# XRACER-FMU-R07.net
KiCad netlist of a schematic drawn in Altium Designer
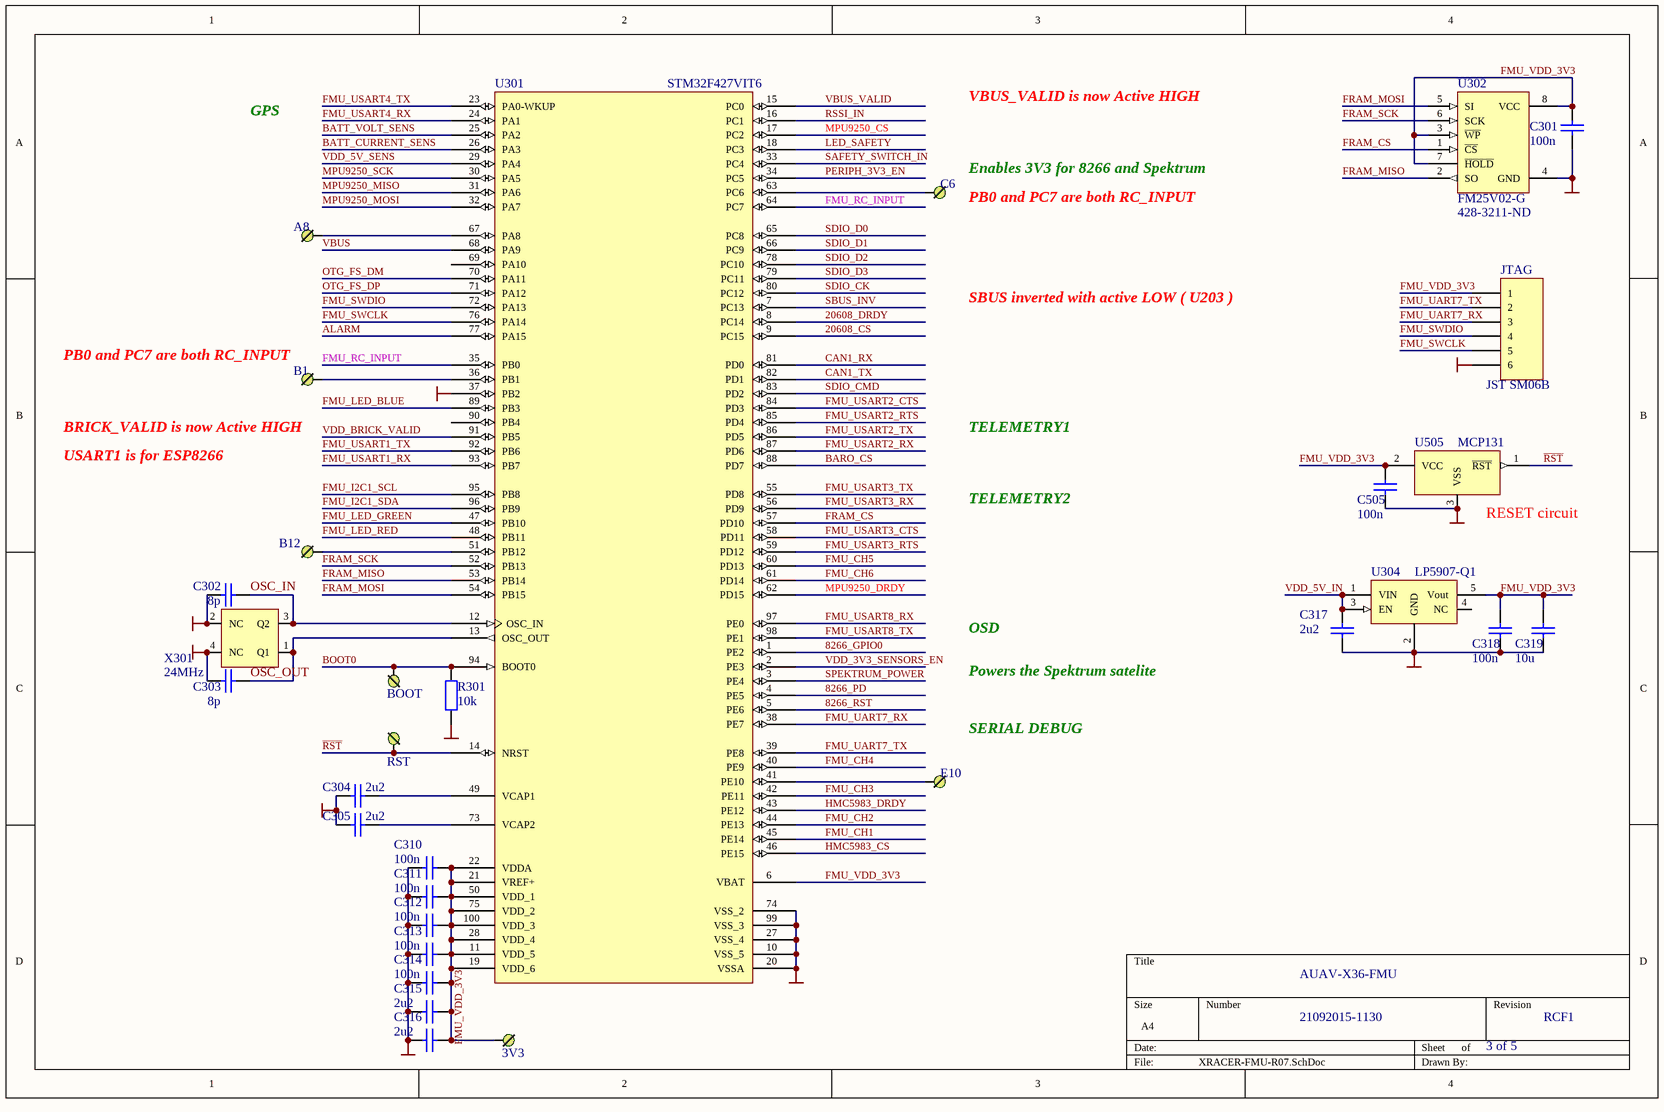
[diagram p0: XRACER-FMU-R07.SchDoc]

(export (version "E")
  (design (tool "Eeschema 10.0.6"))
  (components
    (comp (ref "3V3") (value "3V3") (footprint "PAD1") (libsource (lib "My_Altium") (part "PLUG")))
    (comp (ref "A8") (value "BOOT") (footprint "PAD1") (libsource (lib "My_Altium") (part "PLUG")))
    (comp (ref "B1") (value "BOOT") (footprint "PAD1") (libsource (lib "My_Altium") (part "PLUG")))
    (comp (ref "B12") (value "BOOT") (footprint "PAD1") (libsource (lib "My_Altium") (part "PLUG")))
    (comp (ref "BOOT") (value "BOOT") (footprint "PAD1") (libsource (lib "My_Altium") (part "PLUG")))
    (comp (ref "C6") (value "BOOT") (footprint "PAD1") (libsource (lib "My_Altium") (part "PLUG")))
    (comp (ref "C301")
      (value "100n")
      (footprint "0402A")
      (description "Capacitor")
      (fields (field (name "PUBLISHER") "Altium Limited"))
      (libsource (lib "Miscellaneous Devices") (part "Cap"))
    )
    (comp (ref "C302")
      (value "8p")
      (footprint "0603A")
      (description "Capacitor")
      (fields (field (name "PUBLISHER") "Altium Limited"))
      (libsource (lib "Miscellaneous Devices") (part "Cap"))
    )
    (comp (ref "C303")
      (value "8p")
      (footprint "0603A")
      (description "Capacitor")
      (fields (field (name "PUBLISHER") "Altium Limited"))
      (libsource (lib "Miscellaneous Devices") (part "Cap"))
    )
    (comp (ref "C304")
      (value "2u2")
      (footprint "0402A")
      (description "Capacitor")
      (fields (field (name "PUBLISHER") "Altium Limited"))
      (libsource (lib "Miscellaneous Devices") (part "Cap"))
    )
    (comp (ref "C305")
      (value "2u2")
      (footprint "0402A")
      (description "Capacitor")
      (fields (field (name "PUBLISHER") "Altium Limited"))
      (libsource (lib "Miscellaneous Devices") (part "Cap"))
    )
    (comp (ref "C310")
      (value "100n")
      (footprint "0402A")
      (description "Capacitor")
      (fields (field (name "PUBLISHER") "Altium Limited"))
      (libsource (lib "Miscellaneous Devices") (part "Cap"))
    )
    (comp (ref "C311")
      (value "100n")
      (footprint "0402A")
      (description "Capacitor")
      (fields (field (name "PUBLISHER") "Altium Limited"))
      (libsource (lib "Miscellaneous Devices") (part "Cap"))
    )
    (comp (ref "C312")
      (value "100n")
      (footprint "0402A")
      (description "Capacitor")
      (fields (field (name "PUBLISHER") "Altium Limited"))
      (libsource (lib "Miscellaneous Devices") (part "Cap"))
    )
    (comp (ref "C313")
      (value "100n")
      (footprint "0402A")
      (description "Capacitor")
      (fields (field (name "PUBLISHER") "Altium Limited"))
      (libsource (lib "Miscellaneous Devices") (part "Cap"))
    )
    (comp (ref "C314")
      (value "100n")
      (footprint "0402A")
      (description "Capacitor")
      (fields (field (name "PUBLISHER") "Altium Limited"))
      (libsource (lib "Miscellaneous Devices") (part "Cap"))
    )
    (comp (ref "C315")
      (value "2u2")
      (footprint "0402A")
      (description "Capacitor")
      (fields (field (name "PUBLISHER") "Altium Limited"))
      (libsource (lib "Miscellaneous Devices") (part "Cap"))
    )
    (comp (ref "C316")
      (value "2u2")
      (footprint "0402A")
      (description "Capacitor")
      (fields (field (name "PUBLISHER") "Altium Limited"))
      (libsource (lib "Miscellaneous Devices") (part "Cap"))
    )
    (comp (ref "C317")
      (value "2u2")
      (footprint "0603A")
      (description "Capacitor")
      (fields (field (name "PUBLISHER") "Altium Limited"))
      (libsource (lib "Miscellaneous Devices") (part "Cap"))
    )
    (comp (ref "C318")
      (value "100n")
      (footprint "0603A")
      (description "Capacitor")
      (fields (field (name "PUBLISHER") "Altium Limited"))
      (libsource (lib "Miscellaneous Devices") (part "Cap"))
    )
    (comp (ref "C319")
      (value "10u")
      (footprint "0603A")
      (description "Capacitor")
      (fields (field (name "PUBLISHER") "Altium Limited"))
      (libsource (lib "Miscellaneous Devices") (part "Cap"))
    )
    (comp (ref "C505")
      (value "100n")
      (footprint "0402A")
      (description "Capacitor")
      (fields (field (name "PUBLISHER") "Altium Limited"))
      (libsource (lib "Miscellaneous Devices") (part "Cap"))
    )
    (comp (ref "E10") (value "BOOT") (footprint "PAD1") (libsource (lib "My_Altium") (part "PLUG")))
    (comp (ref "JTAG")
      (value "JST SM06B")
      (footprint "SM06B-SRSH-TB")
      (description "Header, 6-Pin")
      (fields (field (name "PUBLISHER") "Altium Limited"))
      (libsource (lib "Miscellaneous Connectors") (part "Header 6"))
    )
    (comp (ref "R301")
      (value "10k")
      (footprint "0402A")
      (description "Resistor")
      (fields (field (name "PUBLISHER") "Altium Limited"))
      (libsource (lib "Miscellaneous Devices") (part "Res2"))
    )
    (comp (ref "RST") (value "BOOT") (footprint "PAD1") (libsource (lib "My_Altium") (part "PLUG")))
    (comp (ref "U301")
      (value "STM32F427VIT6")
      (footprint "LQFP100_L")
      (description "STM32 ARM-based 32-bit MCU with 64 Kbytes Flash, 100-pin LQFP, Industrial Temperature")
      (fields (field (name "PUBLISHER") "Altium Limited"))
      (libsource (lib "ST Microcontroller 32-Bit STM32") (part "STM32F103VBT6"))
    )
    (comp (ref "U302")
      (value "FM25V02-G")
      (footprint "SO-8_N")
      (fields (field (name "SUPPLIER PART NUMBER") "428-3211-ND"))
      (libsource (lib "My_Altium") (part "AT45DB161D-MU"))
    )
    (comp (ref "U304")
      (value "LP5907-Q1")
      (footprint "SOT23-5")
      (libsource (lib "My_Altium") (part "LP5907-Q1"))
    )
    (comp (ref "U505") (value "MCP131") (footprint "SOT-323") (libsource (lib "My_Altium") (part "MCP102")))
    (comp (ref "X301")
      (value "24MHz")
      (footprint "Crystal_2.5x2")
      (libsource (lib "My_Altium") (part "Crystal_4pin"))
    )
  )
  (nets
    (net (code "1") (name "/8266_GPIO0") (class "Default")
      (node (ref "U301") (pin "1") (pinfunction "PE2_1") (pintype "bidirectional"))
    )
    (net (code "2") (name "/8266_PD") (class "Default")
      (node (ref "U301") (pin "4") (pinfunction "PE5_4") (pintype "bidirectional"))
    )
    (net (code "3") (name "/8266_RST") (class "Default")
      (node (ref "U301") (pin "5") (pinfunction "PE6_5") (pintype "bidirectional"))
    )
    (net (code "4") (name "/20608_CS") (class "Default")
      (node (ref "U301") (pin "9") (pinfunction "PC15_9") (pintype "bidirectional"))
    )
    (net (code "5") (name "/20608_DRDY") (class "Default")
      (node (ref "U301") (pin "8") (pinfunction "PC14_8") (pintype "bidirectional"))
    )
    (net (code "6") (name "/ALARM") (class "Default")
      (node (ref "U301") (pin "77") (pinfunction "PA15_77") (pintype "bidirectional"))
    )
    (net (code "7") (name "/BARO_CS") (class "Default")
      (node (ref "U301") (pin "88") (pinfunction "PD7_88") (pintype "bidirectional"))
    )
    (net (code "8") (name "/BATT_CURRENT_SENS") (class "Default")
      (node (ref "U301") (pin "26") (pinfunction "PA3_26") (pintype "bidirectional"))
    )
    (net (code "9") (name "/BATT_VOLT_SENS") (class "Default")
      (node (ref "U301") (pin "25") (pinfunction "PA2_25") (pintype "bidirectional"))
    )
    (net (code "10") (name "/BOOT0") (class "Default")
      (node (ref "BOOT") (pin "1") (pintype "passive"))
      (node (ref "R301") (pin "1") (pinfunction "1_1") (pintype "passive"))
      (node (ref "U301") (pin "94") (pinfunction "BOOT0_94") (pintype "input"))
    )
    (net (code "11") (name "/CAN1_RX") (class "Default")
      (node (ref "U301") (pin "81") (pinfunction "PD0_81") (pintype "bidirectional"))
    )
    (net (code "12") (name "/CAN1_TX") (class "Default")
      (node (ref "U301") (pin "82") (pinfunction "PD1_82") (pintype "bidirectional"))
    )
    (net (code "13") (name "/FMU_CH1") (class "Default")
      (node (ref "U301") (pin "45") (pinfunction "PE14_45") (pintype "bidirectional"))
    )
    (net (code "14") (name "/FMU_CH2") (class "Default")
      (node (ref "U301") (pin "44") (pinfunction "PE13_44") (pintype "bidirectional"))
    )
    (net (code "15") (name "/FMU_CH3") (class "Default")
      (node (ref "U301") (pin "42") (pinfunction "PE11_42") (pintype "bidirectional"))
    )
    (net (code "16") (name "/FMU_CH4") (class "Default")
      (node (ref "U301") (pin "40") (pinfunction "PE9_40") (pintype "bidirectional"))
    )
    (net (code "17") (name "/FMU_CH5") (class "Default")
      (node (ref "U301") (pin "60") (pinfunction "PD13_60") (pintype "bidirectional"))
    )
    (net (code "18") (name "/FMU_CH6") (class "Default")
      (node (ref "U301") (pin "61") (pinfunction "PD14_61") (pintype "bidirectional"))
    )
    (net (code "19") (name "/FMU_I2C1_SCL") (class "Default")
      (node (ref "U301") (pin "95") (pinfunction "PB8_95") (pintype "bidirectional"))
    )
    (net (code "20") (name "/FMU_I2C1_SDA") (class "Default")
      (node (ref "U301") (pin "96") (pinfunction "PB9_96") (pintype "bidirectional"))
    )
    (net (code "21") (name "/FMU_LED_BLUE") (class "Default")
      (node (ref "U301") (pin "89") (pinfunction "PB3_89") (pintype "bidirectional"))
    )
    (net (code "22") (name "/FMU_LED_GREEN") (class "Default")
      (node (ref "U301") (pin "47") (pinfunction "PB10_47") (pintype "bidirectional"))
    )
    (net (code "23") (name "/FMU_LED_RED") (class "Default")
      (node (ref "U301") (pin "48") (pinfunction "PB11_48") (pintype "bidirectional"))
    )
    (net (code "24") (name "/FMU_RC_INPUT") (class "Default")
      (node (ref "U301") (pin "35") (pinfunction "PB0_35") (pintype "bidirectional"))
      (node (ref "U301") (pin "64") (pinfunction "PC7_64") (pintype "bidirectional"))
    )
    (net (code "25") (name "/FMU_SWCLK") (class "Default")
      (node (ref "JTAG") (pin "5") (pinfunction "5_5") (pintype "passive"))
      (node (ref "U301") (pin "76") (pinfunction "PA14_76") (pintype "bidirectional"))
    )
    (net (code "26") (name "/FMU_SWDIO") (class "Default")
      (node (ref "JTAG") (pin "4") (pinfunction "4_4") (pintype "passive"))
      (node (ref "U301") (pin "72") (pinfunction "PA13_72") (pintype "bidirectional"))
    )
    (net (code "27") (name "/FMU_UART7_RX") (class "Default")
      (node (ref "JTAG") (pin "3") (pinfunction "3_3") (pintype "passive"))
      (node (ref "U301") (pin "38") (pinfunction "PE7_38") (pintype "bidirectional"))
    )
    (net (code "28") (name "/FMU_UART7_TX") (class "Default")
      (node (ref "JTAG") (pin "2") (pinfunction "2_2") (pintype "passive"))
      (node (ref "U301") (pin "39") (pinfunction "PE8_39") (pintype "bidirectional"))
    )
    (net (code "29") (name "/FMU_USART1_RX") (class "Default")
      (node (ref "U301") (pin "93") (pinfunction "PB7_93") (pintype "bidirectional"))
    )
    (net (code "30") (name "/FMU_USART1_TX") (class "Default")
      (node (ref "U301") (pin "92") (pinfunction "PB6_92") (pintype "bidirectional"))
    )
    (net (code "31") (name "/FMU_USART2_CTS") (class "Default")
      (node (ref "U301") (pin "84") (pinfunction "PD3_84") (pintype "bidirectional"))
    )
    (net (code "32") (name "/FMU_USART2_RTS") (class "Default")
      (node (ref "U301") (pin "85") (pinfunction "PD4_85") (pintype "bidirectional"))
    )
    (net (code "33") (name "/FMU_USART2_RX") (class "Default")
      (node (ref "U301") (pin "87") (pinfunction "PD6_87") (pintype "bidirectional"))
    )
    (net (code "34") (name "/FMU_USART2_TX") (class "Default")
      (node (ref "U301") (pin "86") (pinfunction "PD5_86") (pintype "bidirectional"))
    )
    (net (code "35") (name "/FMU_USART3_CTS") (class "Default")
      (node (ref "U301") (pin "58") (pinfunction "PD11_58") (pintype "bidirectional"))
    )
    (net (code "36") (name "/FMU_USART3_RTS") (class "Default")
      (node (ref "U301") (pin "59") (pinfunction "PD12_59") (pintype "bidirectional"))
    )
    (net (code "37") (name "/FMU_USART3_RX") (class "Default")
      (node (ref "U301") (pin "56") (pinfunction "PD9_56") (pintype "bidirectional"))
    )
    (net (code "38") (name "/FMU_USART3_TX") (class "Default")
      (node (ref "U301") (pin "55") (pinfunction "PD8_55") (pintype "bidirectional"))
    )
    (net (code "39") (name "/FMU_USART4_RX") (class "Default")
      (node (ref "U301") (pin "24") (pinfunction "PA1_24") (pintype "bidirectional"))
    )
    (net (code "40") (name "/FMU_USART4_TX") (class "Default")
      (node (ref "U301") (pin "23") (pinfunction "PA0-WKUP_23") (pintype "bidirectional"))
    )
    (net (code "41") (name "/FMU_USART8_RX") (class "Default")
      (node (ref "U301") (pin "97") (pinfunction "PE0_97") (pintype "bidirectional"))
    )
    (net (code "42") (name "/FMU_USART8_TX") (class "Default")
      (node (ref "U301") (pin "98") (pinfunction "PE1_98") (pintype "bidirectional"))
    )
    (net (code "43") (name "/FMU_VDD_3V3") (class "Default")
      (node (ref "3V3") (pin "1") (pintype "passive"))
      (node (ref "C301") (pin "2") (pinfunction "2_2") (pintype "passive"))
      (node (ref "C310") (pin "2") (pinfunction "2_2") (pintype "passive"))
      (node (ref "C311") (pin "2") (pinfunction "2_2") (pintype "passive"))
      (node (ref "C312") (pin "2") (pinfunction "2_2") (pintype "passive"))
      (node (ref "C313") (pin "2") (pinfunction "2_2") (pintype "passive"))
      (node (ref "C314") (pin "2") (pinfunction "2_2") (pintype "passive"))
      (node (ref "C315") (pin "2") (pinfunction "2_2") (pintype "passive"))
      (node (ref "C316") (pin "2") (pinfunction "2_2") (pintype "passive"))
      (node (ref "C318") (pin "2") (pinfunction "2_2") (pintype "passive"))
      (node (ref "C319") (pin "2") (pinfunction "2_2") (pintype "passive"))
      (node (ref "C505") (pin "2") (pinfunction "2_2") (pintype "passive"))
      (node (ref "JTAG") (pin "1") (pinfunction "1_1") (pintype "passive"))
      (node (ref "U301") (pin "100") (pinfunction "VDD_3_100") (pintype "power_in"))
      (node (ref "U301") (pin "11") (pinfunction "VDD_5_11") (pintype "power_in"))
      (node (ref "U301") (pin "19") (pinfunction "VDD_6_19") (pintype "power_in"))
      (node (ref "U301") (pin "21") (pinfunction "VREF+_21") (pintype "power_in"))
      (node (ref "U301") (pin "22") (pinfunction "VDDA_22") (pintype "power_in"))
      (node (ref "U301") (pin "28") (pinfunction "VDD_4_28") (pintype "power_in"))
      (node (ref "U301") (pin "50") (pinfunction "VDD_1_50") (pintype "power_in"))
      (node (ref "U301") (pin "6") (pinfunction "VBAT_6") (pintype "power_in"))
      (node (ref "U301") (pin "75") (pinfunction "VDD_2_75") (pintype "power_in"))
      (node (ref "U302") (pin "3") (pinfunction "~{WP}_3") (pintype "input"))
      (node (ref "U302") (pin "7") (pinfunction "~{HOLD}_7") (pintype "passive"))
      (node (ref "U302") (pin "8") (pinfunction "VCC_8") (pintype "power_in"))
      (node (ref "U304") (pin "5") (pinfunction "Vout_5") (pintype "power_in"))
      (node (ref "U505") (pin "2") (pinfunction "VCC_2") (pintype "power_in"))
    )
    (net (code "44") (name "/FRAM_CS") (class "Default")
      (node (ref "U301") (pin "57") (pinfunction "PD10_57") (pintype "bidirectional"))
      (node (ref "U302") (pin "1") (pinfunction "~{CS}_1") (pintype "input"))
    )
    (net (code "45") (name "/FRAM_MISO") (class "Default")
      (node (ref "U301") (pin "53") (pinfunction "PB14_53") (pintype "bidirectional"))
      (node (ref "U302") (pin "2") (pinfunction "SO_2") (pintype "output"))
    )
    (net (code "46") (name "/FRAM_MOSI") (class "Default")
      (node (ref "U301") (pin "54") (pinfunction "PB15_54") (pintype "bidirectional"))
      (node (ref "U302") (pin "5") (pinfunction "SI_5") (pintype "input"))
    )
    (net (code "47") (name "/FRAM_SCK") (class "Default")
      (node (ref "U301") (pin "52") (pinfunction "PB13_52") (pintype "bidirectional"))
      (node (ref "U302") (pin "6") (pinfunction "SCK_6") (pintype "input"))
    )
    (net (code "48") (name "/HMC5983_CS") (class "Default")
      (node (ref "U301") (pin "46") (pinfunction "PE15_46") (pintype "bidirectional"))
    )
    (net (code "49") (name "/HMC5983_DRDY") (class "Default")
      (node (ref "U301") (pin "43") (pinfunction "PE12_43") (pintype "bidirectional"))
    )
    (net (code "50") (name "/LED_SAFETY") (class "Default")
      (node (ref "U301") (pin "18") (pinfunction "PC3_18") (pintype "bidirectional"))
    )
    (net (code "51") (name "/MPU9250_CS") (class "Default")
      (node (ref "U301") (pin "17") (pinfunction "PC2_17") (pintype "bidirectional"))
    )
    (net (code "52") (name "/MPU9250_DRDY") (class "Default")
      (node (ref "U301") (pin "62") (pinfunction "PD15_62") (pintype "bidirectional"))
    )
    (net (code "53") (name "/MPU9250_MISO") (class "Default")
      (node (ref "U301") (pin "31") (pinfunction "PA6_31") (pintype "bidirectional"))
    )
    (net (code "54") (name "/MPU9250_MOSI") (class "Default")
      (node (ref "U301") (pin "32") (pinfunction "PA7_32") (pintype "bidirectional"))
    )
    (net (code "55") (name "/MPU9250_SCK") (class "Default")
      (node (ref "U301") (pin "30") (pinfunction "PA5_30") (pintype "bidirectional"))
    )
    (net (code "56") (name "/OSC_IN") (class "Default")
      (node (ref "C302") (pin "2") (pinfunction "2_2") (pintype "passive"))
      (node (ref "U301") (pin "12") (pinfunction "OSC_IN_12") (pintype "input"))
      (node (ref "X301") (pin "3") (pinfunction "Q2_3") (pintype "passive"))
    )
    (net (code "57") (name "/OSC_OUT") (class "Default")
      (node (ref "C303") (pin "2") (pinfunction "2_2") (pintype "passive"))
      (node (ref "U301") (pin "13") (pinfunction "OSC_OUT_13") (pintype "output"))
      (node (ref "X301") (pin "1") (pinfunction "Q1_1") (pintype "passive"))
    )
    (net (code "58") (name "/OTG_FS_DM") (class "Default")
      (node (ref "U301") (pin "70") (pinfunction "PA11_70") (pintype "bidirectional"))
    )
    (net (code "59") (name "/OTG_FS_DP") (class "Default")
      (node (ref "U301") (pin "71") (pinfunction "PA12_71") (pintype "bidirectional"))
    )
    (net (code "60") (name "/PERIPH_3V3_EN") (class "Default")
      (node (ref "U301") (pin "34") (pinfunction "PC5_34") (pintype "bidirectional"))
    )
    (net (code "61") (name "/RSSI_IN") (class "Default")
      (node (ref "U301") (pin "16") (pinfunction "PC1_16") (pintype "bidirectional"))
    )
    (net (code "62") (name "/SAFETY_SWITCH_IN") (class "Default")
      (node (ref "U301") (pin "33") (pinfunction "PC4_33") (pintype "bidirectional"))
    )
    (net (code "63") (name "/SBUS_INV") (class "Default")
      (node (ref "U301") (pin "7") (pinfunction "PC13_7") (pintype "bidirectional"))
    )
    (net (code "64") (name "/SDIO_CK") (class "Default")
      (node (ref "U301") (pin "80") (pinfunction "PC12_80") (pintype "bidirectional"))
    )
    (net (code "65") (name "/SDIO_CMD") (class "Default")
      (node (ref "U301") (pin "83") (pinfunction "PD2_83") (pintype "bidirectional"))
    )
    (net (code "66") (name "/SDIO_D0") (class "Default")
      (node (ref "U301") (pin "65") (pinfunction "PC8_65") (pintype "bidirectional"))
    )
    (net (code "67") (name "/SDIO_D1") (class "Default")
      (node (ref "U301") (pin "66") (pinfunction "PC9_66") (pintype "bidirectional"))
    )
    (net (code "68") (name "/SDIO_D2") (class "Default")
      (node (ref "U301") (pin "78") (pinfunction "PC10_78") (pintype "bidirectional"))
    )
    (net (code "69") (name "/SDIO_D3") (class "Default")
      (node (ref "U301") (pin "79") (pinfunction "PC11_79") (pintype "bidirectional"))
    )
    (net (code "70") (name "/SPEKTRUM_POWER") (class "Default")
      (node (ref "U301") (pin "3") (pinfunction "PE4_3") (pintype "bidirectional"))
    )
    (net (code "71") (name "/VBUS") (class "Default")
      (node (ref "U301") (pin "68") (pinfunction "PA9_68") (pintype "bidirectional"))
    )
    (net (code "72") (name "/VBUS_VALID") (class "Default")
      (node (ref "U301") (pin "15") (pinfunction "PC0_15") (pintype "bidirectional"))
    )
    (net (code "73") (name "/VDD_3V3_SENSORS_EN") (class "Default")
      (node (ref "U301") (pin "2") (pinfunction "PE3_2") (pintype "bidirectional"))
    )
    (net (code "74") (name "/VDD_5V_IN") (class "Default")
      (node (ref "C317") (pin "2") (pinfunction "2_2") (pintype "passive"))
      (node (ref "U304") (pin "1") (pinfunction "VIN_1") (pintype "power_in"))
      (node (ref "U304") (pin "3") (pinfunction "EN_3") (pintype "input"))
    )
    (net (code "75") (name "/VDD_5V_SENS") (class "Default")
      (node (ref "U301") (pin "29") (pinfunction "PA4_29") (pintype "bidirectional"))
    )
    (net (code "76") (name "/VDD_BRICK_VALID") (class "Default")
      (node (ref "U301") (pin "91") (pinfunction "PB5_91") (pintype "bidirectional"))
    )
    (net (code "77") (name "/~{RST}") (class "Default")
      (node (ref "RST") (pin "1") (pintype "passive"))
      (node (ref "U301") (pin "14") (pinfunction "NRST_14") (pintype "bidirectional"))
      (node (ref "U505") (pin "1") (pinfunction "~{RST}_1") (pintype "output"))
    )
    (net (code "78") (name "GND") (class "Default")
      (node (ref "C301") (pin "1") (pinfunction "1_1") (pintype "passive"))
      (node (ref "C302") (pin "1") (pinfunction "1_1") (pintype "passive"))
      (node (ref "C303") (pin "1") (pinfunction "1_1") (pintype "passive"))
      (node (ref "C304") (pin "2") (pinfunction "2_2") (pintype "passive"))
      (node (ref "C305") (pin "2") (pinfunction "2_2") (pintype "passive"))
      (node (ref "C310") (pin "1") (pinfunction "1_1") (pintype "passive"))
      (node (ref "C311") (pin "1") (pinfunction "1_1") (pintype "passive"))
      (node (ref "C312") (pin "1") (pinfunction "1_1") (pintype "passive"))
      (node (ref "C313") (pin "1") (pinfunction "1_1") (pintype "passive"))
      (node (ref "C314") (pin "1") (pinfunction "1_1") (pintype "passive"))
      (node (ref "C315") (pin "1") (pinfunction "1_1") (pintype "passive"))
      (node (ref "C316") (pin "1") (pinfunction "1_1") (pintype "passive"))
      (node (ref "C317") (pin "1") (pinfunction "1_1") (pintype "passive"))
      (node (ref "C318") (pin "1") (pinfunction "1_1") (pintype "passive"))
      (node (ref "C319") (pin "1") (pinfunction "1_1") (pintype "passive"))
      (node (ref "C505") (pin "1") (pinfunction "1_1") (pintype "passive"))
      (node (ref "JTAG") (pin "6") (pinfunction "6_6") (pintype "passive"))
      (node (ref "R301") (pin "2") (pinfunction "2_2") (pintype "passive"))
      (node (ref "U301") (pin "10") (pinfunction "VSS_5_10") (pintype "power_in"))
      (node (ref "U301") (pin "20") (pinfunction "VSSA_20") (pintype "power_in"))
      (node (ref "U301") (pin "27") (pinfunction "VSS_4_27") (pintype "power_in"))
      (node (ref "U301") (pin "37") (pinfunction "PB2_37") (pintype "bidirectional"))
      (node (ref "U301") (pin "74") (pinfunction "VSS_2_74") (pintype "power_in"))
      (node (ref "U301") (pin "99") (pinfunction "VSS_3_99") (pintype "power_in"))
      (node (ref "U302") (pin "4") (pinfunction "GND_4") (pintype "power_in"))
      (node (ref "U304") (pin "2") (pinfunction "GND_2") (pintype "power_in"))
      (node (ref "U505") (pin "3") (pinfunction "VSS_3") (pintype "power_in"))
      (node (ref "X301") (pin "2") (pinfunction "NC_2") (pintype "passive"))
      (node (ref "X301") (pin "4") (pinfunction "NC_4") (pintype "passive"))
    )
    (net (code "79") (name "Net-(U301-PA8)") (class "Default")
      (node (ref "A8") (pin "1") (pintype "passive"))
      (node (ref "U301") (pin "67") (pinfunction "PA8_67") (pintype "bidirectional"))
    )
    (net (code "80") (name "Net-(U301-PB1)") (class "Default")
      (node (ref "B1") (pin "1") (pintype "passive"))
      (node (ref "U301") (pin "36") (pinfunction "PB1_36") (pintype "bidirectional"))
    )
    (net (code "81") (name "Net-(U301-PB12)") (class "Default")
      (node (ref "B12") (pin "1") (pintype "passive"))
      (node (ref "U301") (pin "51") (pinfunction "PB12_51") (pintype "bidirectional"))
    )
    (net (code "82") (name "Net-(U301-PC6)") (class "Default")
      (node (ref "C6") (pin "1") (pintype "passive"))
      (node (ref "U301") (pin "63") (pinfunction "PC6_63") (pintype "bidirectional"))
    )
    (net (code "83") (name "Net-(U301-PE10)") (class "Default")
      (node (ref "E10") (pin "1") (pintype "passive"))
      (node (ref "U301") (pin "41") (pinfunction "PE10_41") (pintype "bidirectional"))
    )
    (net (code "84") (name "Net-(U301-VCAP1)") (class "Default")
      (node (ref "C304") (pin "1") (pinfunction "1_1") (pintype "passive"))
      (node (ref "U301") (pin "49") (pinfunction "VCAP1_49") (pintype "passive"))
    )
    (net (code "85") (name "Net-(U301-VCAP2)") (class "Default")
      (node (ref "C305") (pin "1") (pinfunction "1_1") (pintype "passive"))
      (node (ref "U301") (pin "73") (pinfunction "VCAP2_73") (pintype "passive"))
    )
    (net (code "86") (name "unconnected-(U301-PA10-Pad69)") (class "Default")
      (node (ref "U301") (pin "69") (pinfunction "PA10_69") (pintype "bidirectional"))
    )
    (net (code "87") (name "unconnected-(U301-PB4-Pad90)") (class "Default")
      (node (ref "U301") (pin "90") (pinfunction "PB4_90") (pintype "bidirectional"))
    )
    (net (code "88") (name "unconnected-(U304-NC-Pad4)") (class "Default")
      (node (ref "U304") (pin "4") (pinfunction "NC_4") (pintype "passive"))
    )
  )
)
